# dummy_load.net
KiCad netlist of a schematic drawn in EAGLE
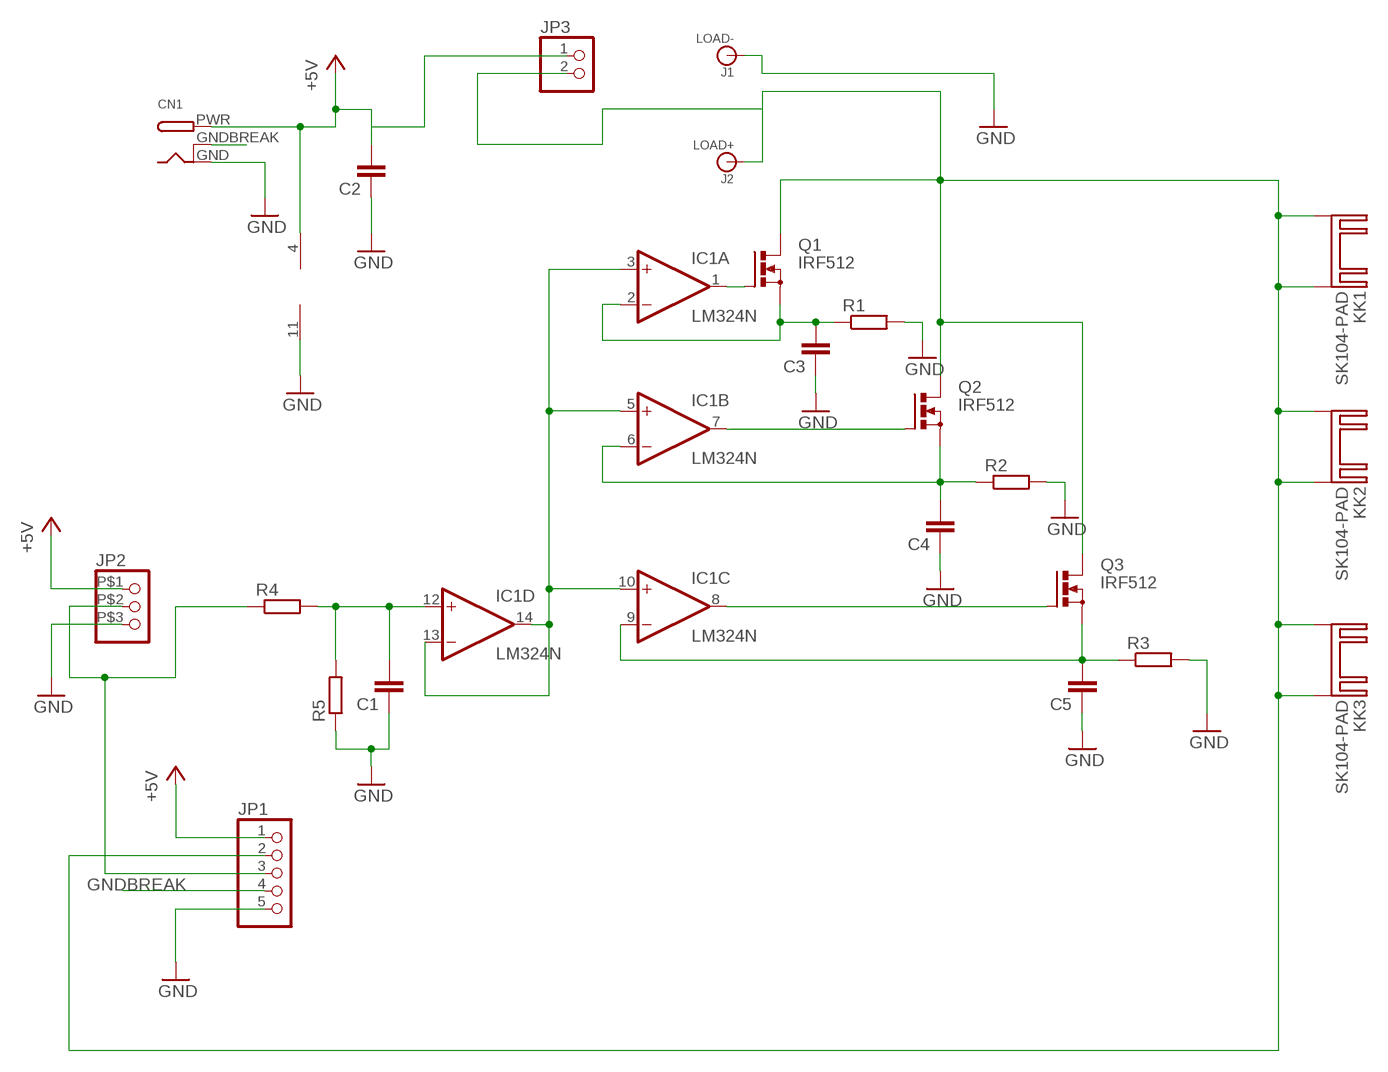
[diagram p0: schematic, sheet 1]

(export (version "E")
  (design (tool "Eeschema 10.0.6"))
  (components
    (comp (ref "C1")
      (value "C-EUC0805")
      (footprint "eagle-import:C0805")
      (libsource (lib "eagle-import") (part "C-EUC0805"))
    )
    (comp (ref "C2")
      (value "C-EUC0805")
      (footprint "eagle-import:C0805")
      (libsource (lib "eagle-import") (part "C-EUC0805"))
    )
    (comp (ref "C3")
      (value "C-EUC0805")
      (footprint "eagle-import:C0805")
      (libsource (lib "eagle-import") (part "C-EUC0805"))
    )
    (comp (ref "C4")
      (value "C-EUC0805")
      (footprint "eagle-import:C0805")
      (libsource (lib "eagle-import") (part "C-EUC0805"))
    )
    (comp (ref "C5")
      (value "C-EUC0805")
      (footprint "eagle-import:C0805")
      (libsource (lib "eagle-import") (part "C-EUC0805"))
    )
    (comp (ref "CN1")
      (value "DCBARRELPTH")
      (footprint "eagle-import:DCJACK_2MM_PTH")
      (libsource (lib "eagle-import") (part "DCBARRELPTH"))
    )
    (comp (ref "IC1")
      (value "LM324N")
      (footprint "eagle-import:DIL14")
      (libsource (lib "eagle-import") (part "LM324N"))
    )
    (comp (ref "J1")
      (value "LOAD-")
      (footprint "eagle-import:BANANA_CONN")
      (libsource (lib "eagle-import") (part "BANANA_CONN"))
    )
    (comp (ref "J2")
      (value "LOAD+")
      (footprint "eagle-import:BANANA_CONN")
      (libsource (lib "eagle-import") (part "BANANA_CONN"))
    )
    (comp (ref "JP1")
      (value "PINHD-1X5/90")
      (footprint "eagle-import:1X05_90")
      (libsource (lib "eagle-import") (part "PINHD-1X5/90"))
    )
    (comp (ref "JP2")
      (value "PINHD-1X35.08")
      (footprint "eagle-import:1X03_5.08")
      (libsource (lib "eagle-import") (part "PINHD-1X35.08"))
    )
    (comp (ref "JP3")
      (value "PINHD-1X2")
      (footprint "eagle-import:1X02")
      (libsource (lib "eagle-import") (part "PINHD-1X2"))
    )
    (comp (ref "KK1")
      (value "SK104-PAD")
      (footprint "eagle-import:SK104-PAD")
      (libsource (lib "eagle-import") (part "SK104-PAD"))
    )
    (comp (ref "KK2")
      (value "SK104-PAD")
      (footprint "eagle-import:SK104-PAD")
      (libsource (lib "eagle-import") (part "SK104-PAD"))
    )
    (comp (ref "KK3")
      (value "SK104-PAD")
      (footprint "eagle-import:SK104-PAD")
      (libsource (lib "eagle-import") (part "SK104-PAD"))
    )
    (comp (ref "Q1")
      (value "IRF512")
      (footprint "eagle-import:TO220BV")
      (libsource (lib "eagle-import") (part "IRF512"))
    )
    (comp (ref "Q2")
      (value "IRF512")
      (footprint "eagle-import:TO220BV")
      (libsource (lib "eagle-import") (part "IRF512"))
    )
    (comp (ref "Q3")
      (value "IRF512")
      (footprint "eagle-import:TO220BV")
      (libsource (lib "eagle-import") (part "IRF512"))
    )
    (comp (ref "R1")
      (value "R-EU_VTA52")
      (footprint "eagle-import:VTA52")
      (libsource (lib "eagle-import") (part "R-EU_VTA52"))
    )
    (comp (ref "R2")
      (value "R-EU_VTA52")
      (footprint "eagle-import:VTA52")
      (libsource (lib "eagle-import") (part "R-EU_VTA52"))
    )
    (comp (ref "R3")
      (value "R-EU_VTA52")
      (footprint "eagle-import:VTA52")
      (libsource (lib "eagle-import") (part "R-EU_VTA52"))
    )
    (comp (ref "R4")
      (value "R-EU_R0805")
      (footprint "eagle-import:R0805")
      (libsource (lib "eagle-import") (part "resistor_R-EU_R0805"))
    )
    (comp (ref "R5")
      (value "R-EU_R0805")
      (footprint "eagle-import:R0805")
      (libsource (lib "eagle-import") (part "resistor_R-EU_R0805"))
    )
  )
  (nets
    (net (code "1") (name "+5V") (class "Default")
      (node (ref "C2") (pin "2") (pinfunction "2_2") (pintype "passive"))
      (node (ref "CN1") (pin "PWR") (pinfunction "PWR_PWR") (pintype "power_in"))
      (node (ref "IC1") (pin "4") (pinfunction "V+_4") (pintype "power_in"))
      (node (ref "JP1") (pin "1") (pinfunction "1_1") (pintype "passive"))
      (node (ref "JP2") (pin "P$1") (pinfunction "1_P$1") (pintype "passive"))
      (node (ref "JP3") (pin "1") (pinfunction "1_1") (pintype "passive"))
    )
    (net (code "2") (name "/GNDBREAK") (class "Default")
      (node (ref "CN1") (pin "GNDBREAK") (pinfunction "GNDBREAK_GNDBREAK") (pintype "power_in"))
      (node (ref "JP1") (pin "4") (pinfunction "4_4") (pintype "passive"))
    )
    (net (code "3") (name "GND") (class "Default")
      (node (ref "C1") (pin "1") (pinfunction "1_1") (pintype "passive"))
      (node (ref "C2") (pin "1") (pinfunction "1_1") (pintype "passive"))
      (node (ref "C3") (pin "1") (pinfunction "1_1") (pintype "passive"))
      (node (ref "C4") (pin "1") (pinfunction "1_1") (pintype "passive"))
      (node (ref "C5") (pin "1") (pinfunction "1_1") (pintype "passive"))
      (node (ref "CN1") (pin "GND") (pinfunction "GND_GND") (pintype "power_in"))
      (node (ref "IC1") (pin "11") (pinfunction "V-_11") (pintype "power_in"))
      (node (ref "J1") (pin "P$1") (pinfunction "1_P$1") (pintype "passive"))
      (node (ref "JP1") (pin "5") (pinfunction "5_5") (pintype "passive"))
      (node (ref "JP2") (pin "P$3") (pinfunction "3_P$3") (pintype "passive"))
      (node (ref "R1") (pin "2") (pinfunction "2_2") (pintype "passive"))
      (node (ref "R2") (pin "2") (pinfunction "2_2") (pintype "passive"))
      (node (ref "R3") (pin "2") (pinfunction "2_2") (pintype "passive"))
      (node (ref "R5") (pin "1") (pinfunction "1_1") (pintype "passive"))
    )
    (net (code "4") (name "Net-(IC1A-+IN)") (class "Default")
      (node (ref "IC1") (pin "10") (pinfunction "+IN_10") (pintype "input"))
      (node (ref "IC1") (pin "13") (pinfunction "-IN_13") (pintype "input"))
      (node (ref "IC1") (pin "14") (pinfunction "OUT_14") (pintype "output"))
      (node (ref "IC1") (pin "3") (pinfunction "+IN_3") (pintype "input"))
      (node (ref "IC1") (pin "5") (pinfunction "+IN_5") (pintype "input"))
    )
    (net (code "5") (name "Net-(IC1A--IN)") (class "Default")
      (node (ref "C3") (pin "2") (pinfunction "2_2") (pintype "passive"))
      (node (ref "IC1") (pin "2") (pinfunction "-IN_2") (pintype "input"))
      (node (ref "Q1") (pin "S") (pinfunction "S_S") (pintype "passive"))
      (node (ref "R1") (pin "1") (pinfunction "1_1") (pintype "passive"))
    )
    (net (code "6") (name "Net-(IC1A-OUT)") (class "Default")
      (node (ref "IC1") (pin "1") (pinfunction "OUT_1") (pintype "output"))
      (node (ref "Q1") (pin "G") (pinfunction "G_G") (pintype "passive"))
    )
    (net (code "7") (name "Net-(IC1B--IN)") (class "Default")
      (node (ref "C4") (pin "2") (pinfunction "2_2") (pintype "passive"))
      (node (ref "IC1") (pin "6") (pinfunction "-IN_6") (pintype "input"))
      (node (ref "Q2") (pin "S") (pinfunction "S_S") (pintype "passive"))
      (node (ref "R2") (pin "1") (pinfunction "1_1") (pintype "passive"))
    )
    (net (code "8") (name "Net-(IC1B-OUT)") (class "Default")
      (node (ref "IC1") (pin "7") (pinfunction "OUT_7") (pintype "output"))
      (node (ref "Q2") (pin "G") (pinfunction "G_G") (pintype "passive"))
    )
    (net (code "9") (name "Net-(IC1C--IN)") (class "Default")
      (node (ref "C5") (pin "2") (pinfunction "2_2") (pintype "passive"))
      (node (ref "IC1") (pin "9") (pinfunction "-IN_9") (pintype "input"))
      (node (ref "Q3") (pin "S") (pinfunction "S_S") (pintype "passive"))
      (node (ref "R3") (pin "1") (pinfunction "1_1") (pintype "passive"))
    )
    (net (code "10") (name "Net-(IC1C-OUT)") (class "Default")
      (node (ref "IC1") (pin "8") (pinfunction "OUT_8") (pintype "output"))
      (node (ref "Q3") (pin "G") (pinfunction "G_G") (pintype "passive"))
    )
    (net (code "11") (name "Net-(IC1D-+IN)") (class "Default")
      (node (ref "C1") (pin "2") (pinfunction "2_2") (pintype "passive"))
      (node (ref "IC1") (pin "12") (pinfunction "+IN_12") (pintype "input"))
      (node (ref "R4") (pin "2") (pinfunction "2_2") (pintype "passive"))
      (node (ref "R5") (pin "2") (pinfunction "2_2") (pintype "passive"))
    )
    (net (code "12") (name "Net-(J2-1)") (class "Default")
      (node (ref "J2") (pin "P$1") (pinfunction "1_P$1") (pintype "passive"))
      (node (ref "JP1") (pin "2") (pinfunction "2_2") (pintype "passive"))
      (node (ref "JP3") (pin "2") (pinfunction "2_2") (pintype "passive"))
      (node (ref "KK1") (pin "K1") (pinfunction "K_K1") (pintype "passive"))
      (node (ref "KK1") (pin "K2") (pinfunction "K_K2") (pintype "passive"))
      (node (ref "KK2") (pin "K1") (pinfunction "K_K1") (pintype "passive"))
      (node (ref "KK2") (pin "K2") (pinfunction "K_K2") (pintype "passive"))
      (node (ref "KK3") (pin "K1") (pinfunction "K_K1") (pintype "passive"))
      (node (ref "KK3") (pin "K2") (pinfunction "K_K2") (pintype "passive"))
      (node (ref "Q1") (pin "D") (pinfunction "D_D") (pintype "passive"))
      (node (ref "Q2") (pin "D") (pinfunction "D_D") (pintype "passive"))
      (node (ref "Q3") (pin "D") (pinfunction "D_D") (pintype "passive"))
    )
    (net (code "13") (name "Net-(JP2-2)") (class "Default")
      (node (ref "JP1") (pin "3") (pinfunction "3_3") (pintype "passive"))
      (node (ref "JP2") (pin "P$2") (pinfunction "2_P$2") (pintype "passive"))
      (node (ref "R4") (pin "1") (pinfunction "1_1") (pintype "passive"))
    )
  )
)
